# Snap4.net
KiCad netlist of a schematic drawn in Altium Designer
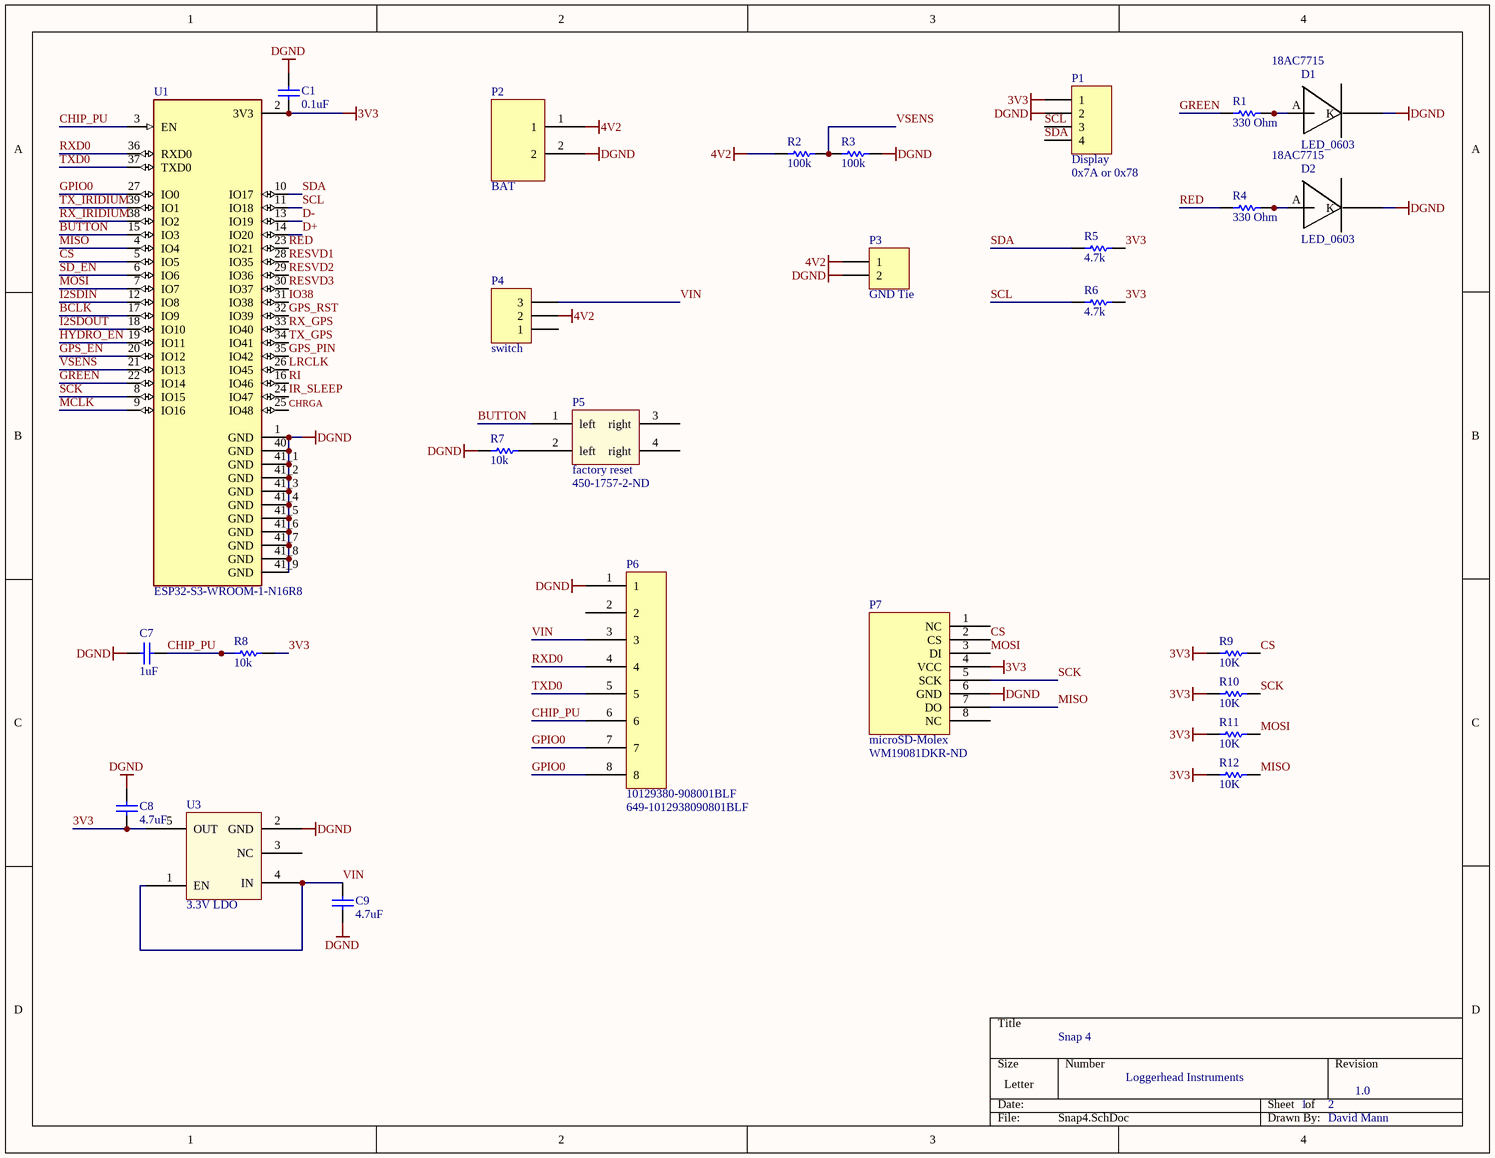
[diagram p0: Snap4.SchDoc]

(export (version "E")
  (design (tool "Eeschema 10.0.6"))
  (components
    (comp (ref "C1")
      (value "0.1uF")
      (footprint "0402")
      (description "Ceramic Chip Capacitor - Standard")
      (fields (field (name "PUBLISHER") "Altium Limited"))
      (libsource (lib "KEMET Chip Capacitor") (part "C0402"))
    )
    (comp (ref "C7")
      (value "1uF")
      (footprint "0402")
      (description "Ceramic Chip Capacitor - Standard")
      (fields (field (name "PUBLISHER") "Altium Limited"))
      (libsource (lib "KEMET Chip Capacitor") (part "C0402"))
    )
    (comp (ref "C8")
      (value "4.7uF")
      (footprint "0402")
      (description "Ceramic Chip Capacitor - Standard")
      (fields (field (name "PUBLISHER") "Altium Limited"))
      (libsource (lib "KEMET Chip Capacitor") (part "C0402"))
    )
    (comp (ref "C9")
      (value "4.7uF")
      (footprint "0402")
      (description "Ceramic Chip Capacitor - Standard")
      (fields (field (name "PUBLISHER") "Altium Limited"))
      (libsource (lib "KEMET Chip Capacitor") (part "C0402"))
    )
    (comp (ref "D1")
      (value "LED_0603")
      (footprint "Diode0603")
      (fields (field (name "SUPPLIER PART NUMBER 1") "18AC7715"))
      (libsource (lib "Loggerhead") (part "LED_0603"))
    )
    (comp (ref "D2")
      (value "LED_0603")
      (footprint "Diode0603")
      (fields (field (name "SUPPLIER PART NUMBER 1") "18AC7715"))
      (libsource (lib "Loggerhead") (part "LED_0603"))
    )
    (comp (ref "P1")
      (value "Display")
      (footprint "HDR1X4")
      (description "Header, 4-Pin")
      (fields (field (name "PUBLISHER") "Altium Limited"))
      (libsource (lib "Miscellaneous Connectors") (part "Header 4"))
    )
    (comp (ref "P2")
      (value "BAT")
      (footprint "HDR_2x1_2mm")
      (libsource (lib "Loggerhead") (part "HDR_2x1_2mm"))
    )
    (comp (ref "P3")
      (value "GND Tie")
      (footprint "HDR1X2")
      (description "Header, 2-Pin")
      (fields (field (name "PUBLISHER") "Altium Limited"))
      (libsource (lib "Miscellaneous Connectors") (part "Header 2"))
    )
    (comp (ref "P4")
      (value "switch")
      (footprint "HDR1X3")
      (description "Header, 3-Pin")
      (fields (field (name "PUBLISHER") "Altium Limited"))
      (libsource (lib "Miscellaneous Connectors") (part "Header 3"))
    )
    (comp (ref "P5")
      (value "factory reset")
      (footprint "SOP4")
      (fields (field (name "SUPPLIER PART NUMBER 1") "450-1757-2-ND"))
      (libsource (lib "Loggerhead") (part "pushbutton"))
    )
    (comp (ref "P6")
      (value "10129380-908001BLF")
      (footprint "Header_8_SMT")
      (description "Surface mount header")
      (fields (field (name "SUPPLIER PART NUMBER 1") "649-1012938090801BLF"))
      (libsource (lib "Loggerhead") (part "Header8_SMT"))
    )
    (comp (ref "P7")
      (value "microSD-Molex")
      (footprint "microSD_Molex_hinged")
      (fields (field (name "SUPPLIER PART NUMBER 1") "WM19081DKR-ND"))
      (libsource (lib "Loggerhead") (part "microSD_Molex_hinged"))
    )
    (comp (ref "R1")
      (value "330 Ohm")
      (footprint "2-0402")
      (fields (field (name "PUBLISHER") "Altium Limited"))
      (libsource (lib "Panasonic Resistor") (part "ERJ2RB"))
    )
    (comp (ref "R2")
      (value "100k")
      (footprint "3-0603")
      (fields (field (name "PUBLISHER") "Altium Limited"))
      (libsource (lib "Panasonic Resistor") (part "ERJ3RK"))
    )
    (comp (ref "R3")
      (value "100k")
      (footprint "3-0603")
      (fields (field (name "PUBLISHER") "Altium Limited"))
      (libsource (lib "Panasonic Resistor") (part "ERJ3RK"))
    )
    (comp (ref "R4")
      (value "330 Ohm")
      (footprint "2-0402")
      (fields (field (name "PUBLISHER") "Altium Limited"))
      (libsource (lib "Panasonic Resistor") (part "ERJ2RB"))
    )
    (comp (ref "R5")
      (value "4.7k")
      (footprint "3-0603")
      (fields (field (name "PUBLISHER") "Altium Limited"))
      (libsource (lib "Panasonic Resistor") (part "ERJ3RK"))
    )
    (comp (ref "R6")
      (value "4.7k")
      (footprint "3-0603")
      (fields (field (name "PUBLISHER") "Altium Limited"))
      (libsource (lib "Panasonic Resistor") (part "ERJ3RK"))
    )
    (comp (ref "R7")
      (value "10k")
      (footprint "2-0402")
      (fields (field (name "PUBLISHER") "Altium Limited"))
      (libsource (lib "Panasonic Resistor") (part "ERJ2RB"))
    )
    (comp (ref "R8")
      (value "10k")
      (footprint "2-0402")
      (fields (field (name "PUBLISHER") "Altium Limited"))
      (libsource (lib "Panasonic Resistor") (part "ERJ2RB"))
    )
    (comp (ref "R9")
      (value "10K")
      (footprint "3-0603")
      (fields (field (name "PUBLISHER") "Altium Limited"))
      (libsource (lib "Panasonic Resistor") (part "ERJ3EK"))
    )
    (comp (ref "R10")
      (value "10K")
      (footprint "3-0603")
      (fields (field (name "PUBLISHER") "Altium Limited"))
      (libsource (lib "Panasonic Resistor") (part "ERJ3EK"))
    )
    (comp (ref "R11")
      (value "10K")
      (footprint "3-0603")
      (fields (field (name "PUBLISHER") "Altium Limited"))
      (libsource (lib "Panasonic Resistor") (part "ERJ3EK"))
    )
    (comp (ref "R12")
      (value "10K")
      (footprint "3-0603")
      (fields (field (name "PUBLISHER") "Altium Limited"))
      (libsource (lib "Panasonic Resistor") (part "ERJ3EK"))
    )
    (comp (ref "U1")
      (value "ESP32-S3-WROOM-1-N16R8")
      (footprint "XCVR_ESP32-S3-WROOM-1-N16R2")
      (description "Bluetooth, WiFi 802.11b/g/n, Bluetooth v5.0 Transceiver Module 2.4GHz PCB Trace Surface Mount")
      (fields (field (name "MP") "ESP32-S3-WROOM-1-N16R2") (field (name "MF") "Espressif Systems"))
      (libsource (lib "ESP32-S3-WROOM-1-N16R2") (part "ESP32-S3-WROOM-1-N16R2"))
    )
    (comp (ref "U3")
      (value "3.3V LDO")
      (footprint "AP7361C-33Y5-13")
      (libsource (lib "Loggerhead") (part "AP7361C-33Y5-13"))
    )
  )
  (nets
    (net (code "1") (name "/BCLK") (class "Default")
      (node (ref "U1") (pin "17") (pinfunction "IO9_17") (pintype "bidirectional"))
    )
    (net (code "2") (name "/BUTTON") (class "Default")
      (node (ref "P5") (pin "1") (pinfunction "left_1") (pintype "passive"))
      (node (ref "U1") (pin "15") (pinfunction "IO3_15") (pintype "bidirectional"))
    )
    (net (code "3") (name "/CHIP_PU") (class "Default")
      (node (ref "C7") (pin "1") (pinfunction "1_1") (pintype "passive"))
      (node (ref "P6") (pin "6") (pinfunction "6_6") (pintype "passive"))
      (node (ref "R8") (pin "2") (pinfunction "2_2") (pintype "passive"))
      (node (ref "U1") (pin "3") (pinfunction "EN_3") (pintype "input"))
    )
    (net (code "4") (name "/CHRGA") (class "Default")
      (node (ref "U1") (pin "25") (pinfunction "IO48_25") (pintype "bidirectional"))
    )
    (net (code "5") (name "/CS") (class "Default")
      (node (ref "P7") (pin "2") (pinfunction "CS_2") (pintype "passive"))
      (node (ref "R9") (pin "2") (pinfunction "2_2") (pintype "passive"))
      (node (ref "U1") (pin "5") (pinfunction "IO5_5") (pintype "bidirectional"))
    )
    (net (code "6") (name "/D+") (class "Default")
      (node (ref "U1") (pin "14") (pinfunction "IO20_14") (pintype "bidirectional"))
    )
    (net (code "7") (name "/D-") (class "Default")
      (node (ref "U1") (pin "13") (pinfunction "IO19_13") (pintype "bidirectional"))
    )
    (net (code "8") (name "/GPIO0") (class "Default")
      (node (ref "P6") (pin "7") (pinfunction "7_7") (pintype "passive"))
      (node (ref "P6") (pin "8") (pinfunction "8_8") (pintype "passive"))
      (node (ref "U1") (pin "27") (pinfunction "IO0_27") (pintype "bidirectional"))
    )
    (net (code "9") (name "/GPS_EN") (class "Default")
      (node (ref "U1") (pin "20") (pinfunction "IO12_20") (pintype "bidirectional"))
    )
    (net (code "10") (name "/GPS_PIN") (class "Default")
      (node (ref "U1") (pin "35") (pinfunction "IO42_35") (pintype "bidirectional"))
    )
    (net (code "11") (name "/GPS_RST") (class "Default")
      (node (ref "U1") (pin "32") (pinfunction "IO39_32") (pintype "bidirectional"))
    )
    (net (code "12") (name "/GREEN") (class "Default")
      (node (ref "R1") (pin "2") (pinfunction "2_2") (pintype "passive"))
      (node (ref "U1") (pin "22") (pinfunction "IO14_22") (pintype "bidirectional"))
    )
    (net (code "13") (name "/HYDRO_EN") (class "Default")
      (node (ref "U1") (pin "19") (pinfunction "IO11_19") (pintype "bidirectional"))
    )
    (net (code "14") (name "/I2SDIN") (class "Default")
      (node (ref "U1") (pin "12") (pinfunction "IO8_12") (pintype "bidirectional"))
    )
    (net (code "15") (name "/I2SDOUT") (class "Default")
      (node (ref "U1") (pin "18") (pinfunction "IO10_18") (pintype "bidirectional"))
    )
    (net (code "16") (name "/IO38") (class "Default")
      (node (ref "U1") (pin "31") (pinfunction "IO38_31") (pintype "bidirectional"))
    )
    (net (code "17") (name "/IR_SLEEP") (class "Default")
      (node (ref "U1") (pin "24") (pinfunction "IO47_24") (pintype "bidirectional"))
    )
    (net (code "18") (name "/LRCLK") (class "Default")
      (node (ref "U1") (pin "26") (pinfunction "IO45_26") (pintype "bidirectional"))
    )
    (net (code "19") (name "/MCLK") (class "Default")
      (node (ref "U1") (pin "9") (pinfunction "IO16_9") (pintype "bidirectional"))
    )
    (net (code "20") (name "/MISO") (class "Default")
      (node (ref "P7") (pin "7") (pinfunction "DO_7") (pintype "passive"))
      (node (ref "R12") (pin "2") (pinfunction "2_2") (pintype "passive"))
      (node (ref "U1") (pin "4") (pinfunction "IO4_4") (pintype "bidirectional"))
    )
    (net (code "21") (name "/MOSI") (class "Default")
      (node (ref "P7") (pin "3") (pinfunction "DI_3") (pintype "passive"))
      (node (ref "R11") (pin "2") (pinfunction "2_2") (pintype "passive"))
      (node (ref "U1") (pin "7") (pinfunction "IO7_7") (pintype "bidirectional"))
    )
    (net (code "22") (name "/RED") (class "Default")
      (node (ref "R4") (pin "2") (pinfunction "2_2") (pintype "passive"))
      (node (ref "U1") (pin "23") (pinfunction "IO21_23") (pintype "bidirectional"))
    )
    (net (code "23") (name "/RESVD1") (class "Default")
      (node (ref "U1") (pin "28") (pinfunction "IO35_28") (pintype "bidirectional"))
    )
    (net (code "24") (name "/RESVD2") (class "Default")
      (node (ref "U1") (pin "29") (pinfunction "IO36_29") (pintype "bidirectional"))
    )
    (net (code "25") (name "/RESVD3") (class "Default")
      (node (ref "U1") (pin "30") (pinfunction "IO37_30") (pintype "bidirectional"))
    )
    (net (code "26") (name "/RI") (class "Default")
      (node (ref "U1") (pin "16") (pinfunction "IO46_16") (pintype "bidirectional"))
    )
    (net (code "27") (name "/RXD0") (class "Default")
      (node (ref "P6") (pin "4") (pinfunction "4_4") (pintype "passive"))
      (node (ref "U1") (pin "36") (pinfunction "RXD0_36") (pintype "bidirectional"))
    )
    (net (code "28") (name "/RX_GPS") (class "Default")
      (node (ref "U1") (pin "33") (pinfunction "IO40_33") (pintype "bidirectional"))
    )
    (net (code "29") (name "/RX_IRIDIUM") (class "Default")
      (node (ref "U1") (pin "38") (pinfunction "IO2_38") (pintype "bidirectional"))
    )
    (net (code "30") (name "/SCK") (class "Default")
      (node (ref "P7") (pin "5") (pinfunction "SCK_5") (pintype "passive"))
      (node (ref "R10") (pin "2") (pinfunction "2_2") (pintype "passive"))
      (node (ref "U1") (pin "8") (pinfunction "IO15_8") (pintype "bidirectional"))
    )
    (net (code "31") (name "/SCL") (class "Default")
      (node (ref "P1") (pin "3") (pinfunction "3_3") (pintype "passive"))
      (node (ref "R6") (pin "1") (pinfunction "1_1") (pintype "passive"))
      (node (ref "U1") (pin "11") (pinfunction "IO18_11") (pintype "bidirectional"))
    )
    (net (code "32") (name "/SDA") (class "Default")
      (node (ref "P1") (pin "4") (pinfunction "4_4") (pintype "passive"))
      (node (ref "R5") (pin "1") (pinfunction "1_1") (pintype "passive"))
      (node (ref "U1") (pin "10") (pinfunction "IO17_10") (pintype "bidirectional"))
    )
    (net (code "33") (name "/SD_EN") (class "Default")
      (node (ref "U1") (pin "6") (pinfunction "IO6_6") (pintype "bidirectional"))
    )
    (net (code "34") (name "/TXD0") (class "Default")
      (node (ref "P6") (pin "5") (pinfunction "5_5") (pintype "passive"))
      (node (ref "U1") (pin "37") (pinfunction "TXD0_37") (pintype "bidirectional"))
    )
    (net (code "35") (name "/TX_GPS") (class "Default")
      (node (ref "U1") (pin "34") (pinfunction "IO41_34") (pintype "bidirectional"))
    )
    (net (code "36") (name "/TX_IRIDIUM") (class "Default")
      (node (ref "U1") (pin "39") (pinfunction "IO1_39") (pintype "bidirectional"))
    )
    (net (code "37") (name "/VIN") (class "Default")
      (node (ref "C9") (pin "1") (pinfunction "1_1") (pintype "passive"))
      (node (ref "P4") (pin "3") (pinfunction "3_3") (pintype "passive"))
      (node (ref "P6") (pin "3") (pinfunction "3_3") (pintype "passive"))
      (node (ref "U3") (pin "1") (pinfunction "EN_1") (pintype "passive"))
      (node (ref "U3") (pin "4") (pinfunction "IN_4") (pintype "passive"))
    )
    (net (code "38") (name "/VSENS") (class "Default")
      (node (ref "R2") (pin "1") (pinfunction "1_1") (pintype "passive"))
      (node (ref "R3") (pin "2") (pinfunction "2_2") (pintype "passive"))
      (node (ref "U1") (pin "21") (pinfunction "IO13_21") (pintype "bidirectional"))
    )
    (net (code "39") (name "3V3") (class "Default")
      (node (ref "C1") (pin "1") (pinfunction "1_1") (pintype "passive"))
      (node (ref "C8") (pin "2") (pinfunction "2_2") (pintype "passive"))
      (node (ref "P1") (pin "1") (pinfunction "1_1") (pintype "passive"))
      (node (ref "P7") (pin "4") (pinfunction "VCC_4") (pintype "passive"))
      (node (ref "R10") (pin "1") (pinfunction "1_1") (pintype "passive"))
      (node (ref "R11") (pin "1") (pinfunction "1_1") (pintype "passive"))
      (node (ref "R12") (pin "1") (pinfunction "1_1") (pintype "passive"))
      (node (ref "R5") (pin "2") (pinfunction "2_2") (pintype "passive"))
      (node (ref "R6") (pin "2") (pinfunction "2_2") (pintype "passive"))
      (node (ref "R8") (pin "1") (pinfunction "1_1") (pintype "passive"))
      (node (ref "R9") (pin "1") (pinfunction "1_1") (pintype "passive"))
      (node (ref "U1") (pin "2") (pinfunction "3V3_2") (pintype "power_in"))
      (node (ref "U3") (pin "5") (pinfunction "OUT_5") (pintype "passive"))
    )
    (net (code "40") (name "4V2") (class "Default")
      (node (ref "P2") (pin "1") (pinfunction "1_1") (pintype "passive"))
      (node (ref "P3") (pin "1") (pinfunction "1_1") (pintype "passive"))
      (node (ref "P4") (pin "2") (pinfunction "2_2") (pintype "passive"))
      (node (ref "R2") (pin "2") (pinfunction "2_2") (pintype "passive"))
    )
    (net (code "41") (name "DGND") (class "Default")
      (node (ref "C1") (pin "2") (pinfunction "2_2") (pintype "passive"))
      (node (ref "C7") (pin "2") (pinfunction "2_2") (pintype "passive"))
      (node (ref "C8") (pin "1") (pinfunction "1_1") (pintype "passive"))
      (node (ref "C9") (pin "2") (pinfunction "2_2") (pintype "passive"))
      (node (ref "D1") (pin "K") (pinfunction "K_K") (pintype "passive"))
      (node (ref "D2") (pin "K") (pinfunction "K_K") (pintype "passive"))
      (node (ref "P1") (pin "2") (pinfunction "2_2") (pintype "passive"))
      (node (ref "P2") (pin "2") (pinfunction "2_2") (pintype "passive"))
      (node (ref "P3") (pin "2") (pinfunction "2_2") (pintype "passive"))
      (node (ref "P6") (pin "1") (pinfunction "1_1") (pintype "passive"))
      (node (ref "P7") (pin "6") (pinfunction "GND_6") (pintype "passive"))
      (node (ref "R3") (pin "1") (pinfunction "1_1") (pintype "passive"))
      (node (ref "R7") (pin "2") (pinfunction "2_2") (pintype "passive"))
      (node (ref "U1") (pin "1") (pinfunction "GND_1") (pintype "power_in"))
      (node (ref "U1") (pin "40") (pinfunction "GND_40") (pintype "power_in"))
      (node (ref "U1") (pin "41_1") (pinfunction "GND_41_1") (pintype "power_in"))
      (node (ref "U1") (pin "41_2") (pinfunction "GND_41_2") (pintype "power_in"))
      (node (ref "U1") (pin "41_3") (pinfunction "GND_41_3") (pintype "power_in"))
      (node (ref "U1") (pin "41_4") (pinfunction "GND_41_4") (pintype "power_in"))
      (node (ref "U1") (pin "41_5") (pinfunction "GND_41_5") (pintype "power_in"))
      (node (ref "U1") (pin "41_6") (pinfunction "GND_41_6") (pintype "power_in"))
      (node (ref "U1") (pin "41_7") (pinfunction "GND_41_7") (pintype "power_in"))
      (node (ref "U1") (pin "41_8") (pinfunction "GND_41_8") (pintype "power_in"))
      (node (ref "U1") (pin "41_9") (pinfunction "GND_41_9") (pintype "power_in"))
      (node (ref "U3") (pin "2") (pinfunction "GND_2") (pintype "passive"))
    )
    (net (code "42") (name "Net-(D1-PadA)") (class "Default")
      (node (ref "D1") (pin "A") (pinfunction "A_A") (pintype "passive"))
      (node (ref "R1") (pin "1") (pinfunction "1_1") (pintype "passive"))
    )
    (net (code "43") (name "Net-(D2-PadA)") (class "Default")
      (node (ref "D2") (pin "A") (pinfunction "A_A") (pintype "passive"))
      (node (ref "R4") (pin "1") (pinfunction "1_1") (pintype "passive"))
    )
    (net (code "44") (name "Net-(P5-left-Pad2)") (class "Default")
      (node (ref "P5") (pin "2") (pinfunction "left_2") (pintype "passive"))
      (node (ref "R7") (pin "1") (pinfunction "1_1") (pintype "passive"))
    )
    (net (code "45") (name "unconnected-(P4-Pad1)") (class "Default")
      (node (ref "P4") (pin "1") (pinfunction "1_1") (pintype "passive"))
    )
    (net (code "46") (name "unconnected-(P5-right-Pad3)") (class "Default")
      (node (ref "P5") (pin "3") (pinfunction "right_3") (pintype "passive"))
    )
    (net (code "47") (name "unconnected-(P5-right-Pad4)") (class "Default")
      (node (ref "P5") (pin "4") (pinfunction "right_4") (pintype "passive"))
    )
    (net (code "48") (name "unconnected-(P6-Pad2)") (class "Default")
      (node (ref "P6") (pin "2") (pinfunction "2_2") (pintype "passive"))
    )
    (net (code "49") (name "unconnected-(P7-NC-Pad1)") (class "Default")
      (node (ref "P7") (pin "1") (pinfunction "NC_1") (pintype "passive"))
    )
    (net (code "50") (name "unconnected-(P7-NC-Pad8)") (class "Default")
      (node (ref "P7") (pin "8") (pinfunction "NC_8") (pintype "passive"))
    )
    (net (code "51") (name "unconnected-(U3-NC-Pad3)") (class "Default")
      (node (ref "U3") (pin "3") (pinfunction "NC_3") (pintype "passive"))
    )
  )
)
